# kalman.net
KiCad netlist of a schematic drawn in EAGLE
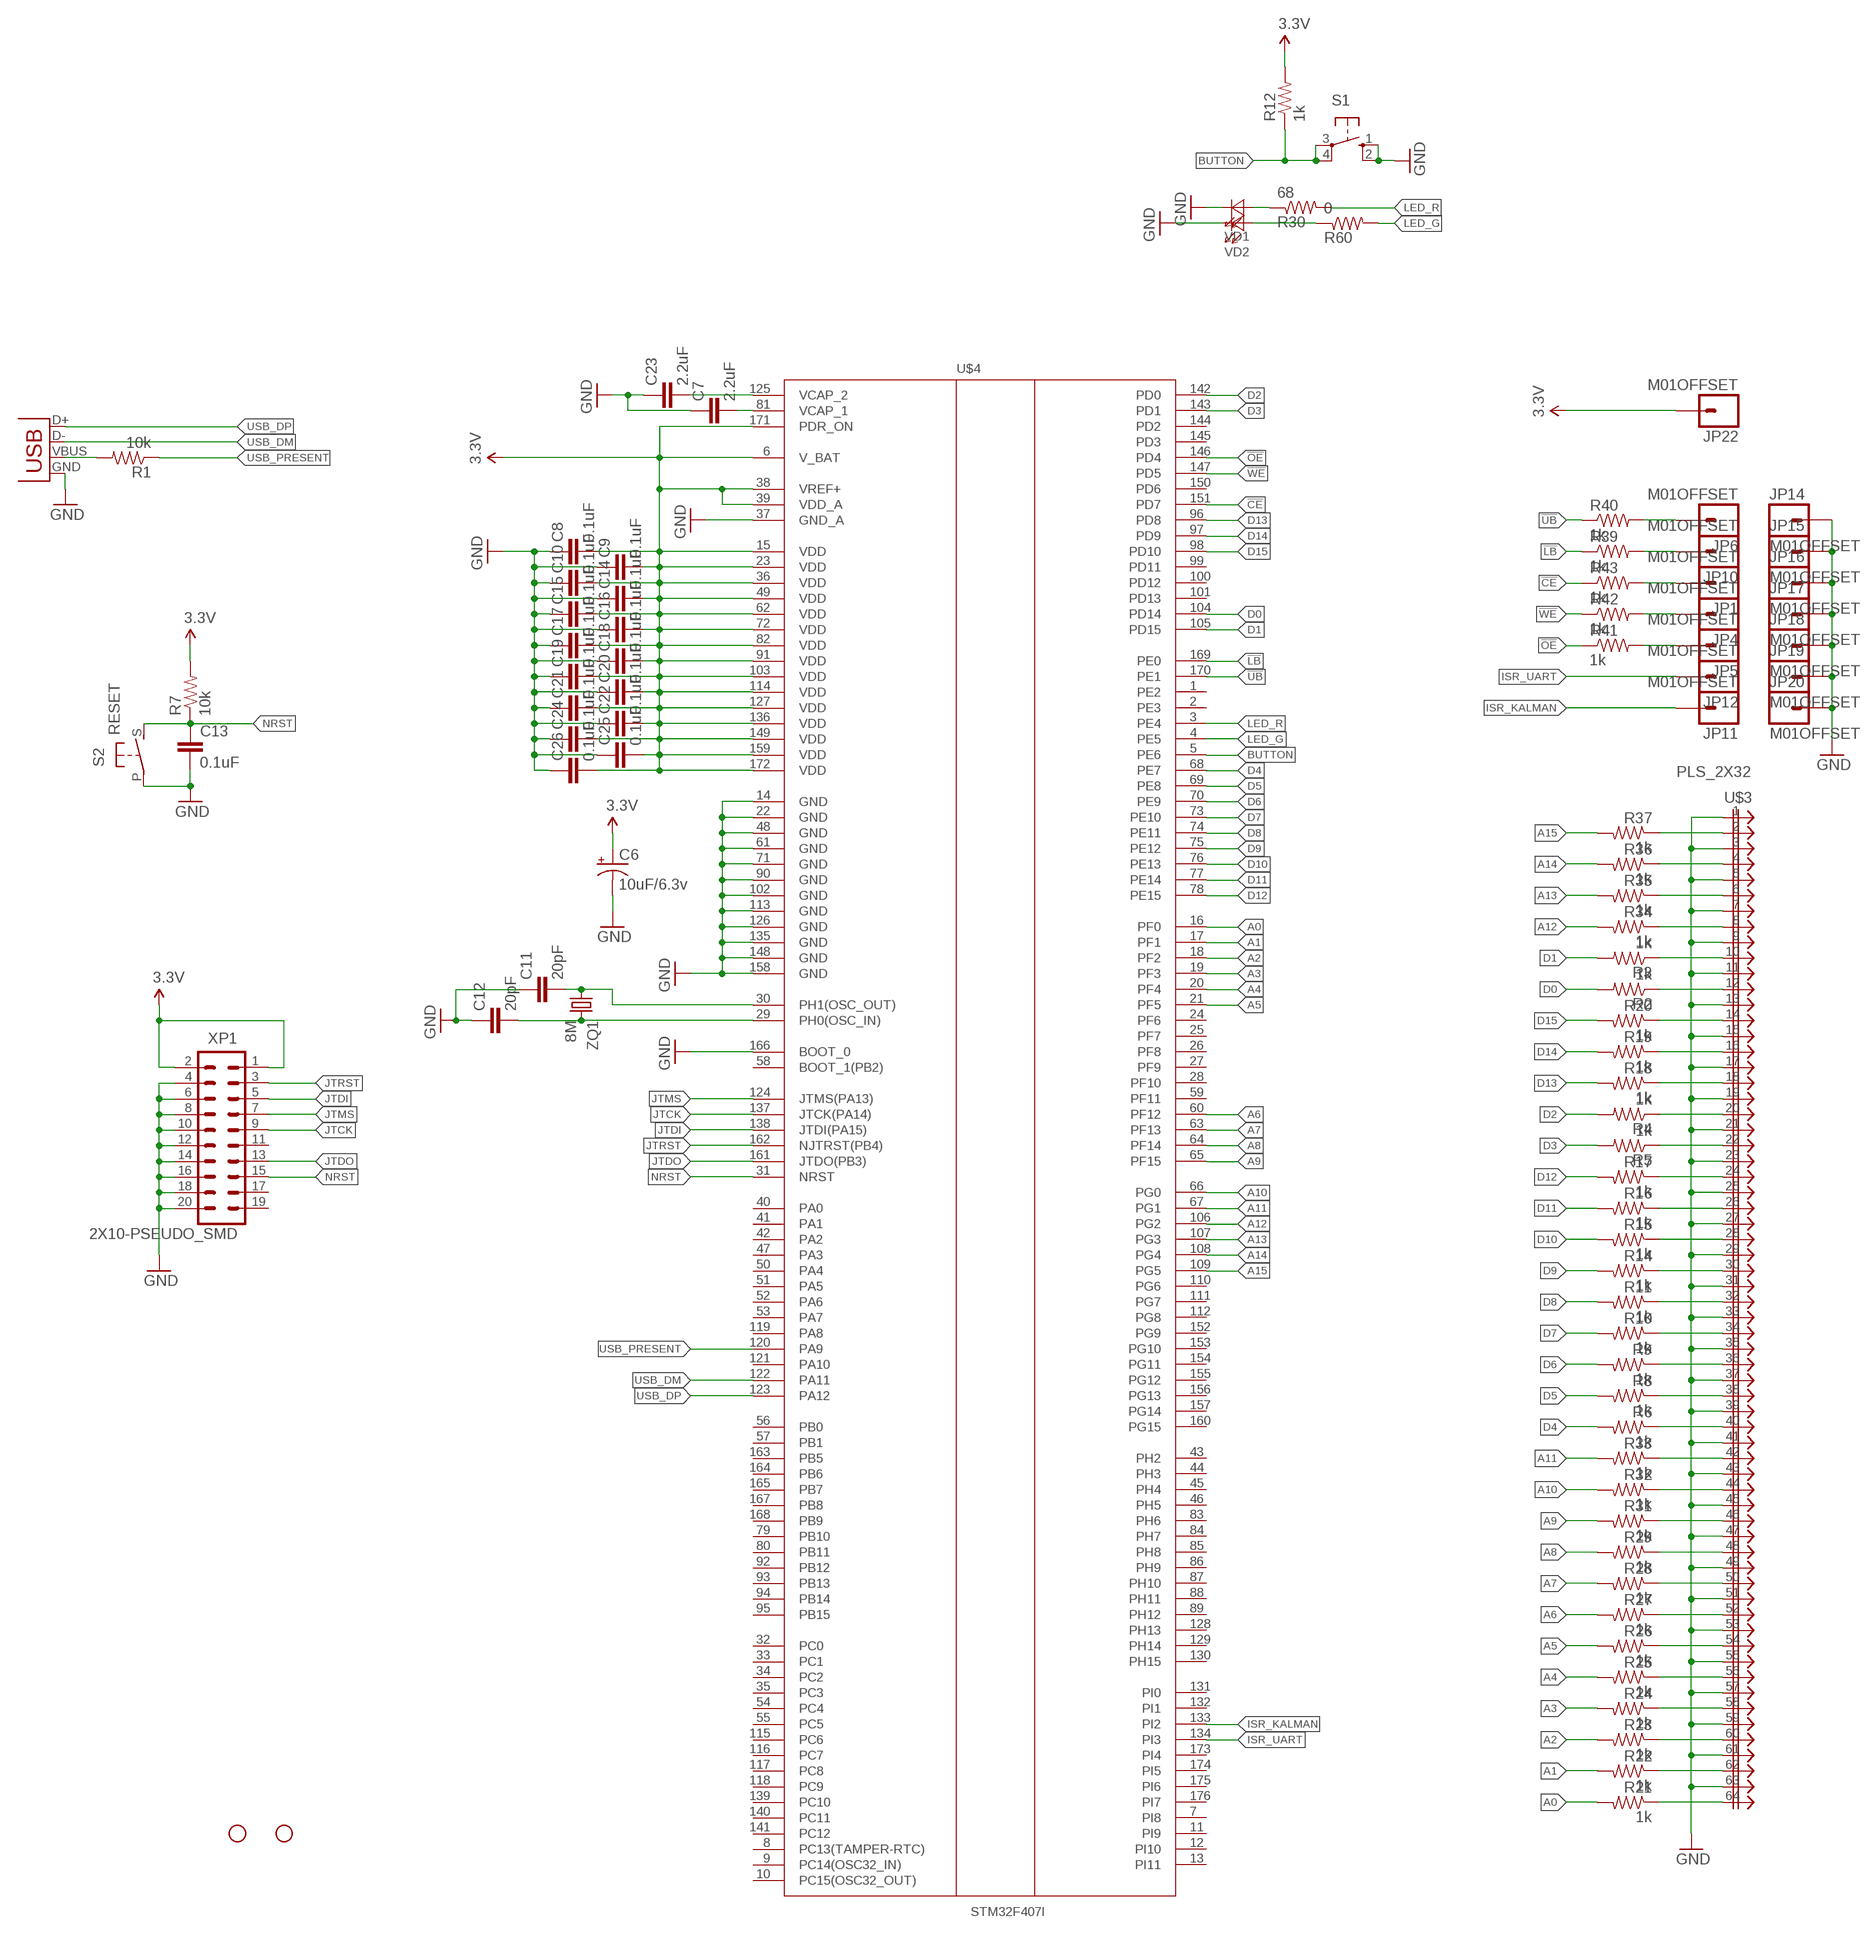
[diagram p0: schematic, sheet 1]

(export (version "E")
  (design (tool "Eeschema 10.0.6"))
  (components
    (comp (ref "C6")
      (value "10uF/6.3v")
      (footprint "eagle-import:EIA3216-KIT")
      (libsource (lib "eagle-import") (part "CAP_POL1206-KIT"))
    )
    (comp (ref "C7")
      (value "2.2uF")
      (footprint "eagle-import:0805")
      (libsource (lib "eagle-import") (part "CAP0805"))
    )
    (comp (ref "C8")
      (value "0.1uF")
      (footprint "eagle-import:0805")
      (libsource (lib "eagle-import") (part "CAP0805"))
    )
    (comp (ref "C9")
      (value "0.1uF")
      (footprint "eagle-import:0805")
      (libsource (lib "eagle-import") (part "CAP0805"))
    )
    (comp (ref "C10")
      (value "0.1uF")
      (footprint "eagle-import:0805")
      (libsource (lib "eagle-import") (part "CAP0805"))
    )
    (comp (ref "C11")
      (value "20pF")
      (footprint "eagle-import:0805")
      (libsource (lib "eagle-import") (part "CAP0805"))
    )
    (comp (ref "C12")
      (value "20pF")
      (footprint "eagle-import:0805")
      (libsource (lib "eagle-import") (part "CAP0805"))
    )
    (comp (ref "C13")
      (value "0.1uF")
      (footprint "eagle-import:0805")
      (libsource (lib "eagle-import") (part "CAP0805"))
    )
    (comp (ref "C14")
      (value "0.1uF")
      (footprint "eagle-import:0805")
      (libsource (lib "eagle-import") (part "CAP0805"))
    )
    (comp (ref "C15")
      (value "0.1uF")
      (footprint "eagle-import:0805")
      (libsource (lib "eagle-import") (part "CAP0805"))
    )
    (comp (ref "C16")
      (value "0.1uF")
      (footprint "eagle-import:0805")
      (libsource (lib "eagle-import") (part "CAP0805"))
    )
    (comp (ref "C17")
      (value "0.1uF")
      (footprint "eagle-import:0805")
      (libsource (lib "eagle-import") (part "CAP0805"))
    )
    (comp (ref "C18")
      (value "0.1uF")
      (footprint "eagle-import:0805")
      (libsource (lib "eagle-import") (part "CAP0805"))
    )
    (comp (ref "C19")
      (value "0.1uF")
      (footprint "eagle-import:0805")
      (libsource (lib "eagle-import") (part "CAP0805"))
    )
    (comp (ref "C20")
      (value "0.1uF")
      (footprint "eagle-import:0805")
      (libsource (lib "eagle-import") (part "CAP0805"))
    )
    (comp (ref "C21")
      (value "0.1uF")
      (footprint "eagle-import:0805")
      (libsource (lib "eagle-import") (part "CAP0805"))
    )
    (comp (ref "C22")
      (value "0.1uF")
      (footprint "eagle-import:0805")
      (libsource (lib "eagle-import") (part "CAP0805"))
    )
    (comp (ref "C23")
      (value "2.2uF")
      (footprint "eagle-import:0805")
      (libsource (lib "eagle-import") (part "CAP0805"))
    )
    (comp (ref "C24")
      (value "0.1uF")
      (footprint "eagle-import:0805")
      (libsource (lib "eagle-import") (part "CAP0805"))
    )
    (comp (ref "C25")
      (value "0.1uF")
      (footprint "eagle-import:0805")
      (libsource (lib "eagle-import") (part "CAP0805"))
    )
    (comp (ref "C26")
      (value "0.1uF")
      (footprint "eagle-import:0805")
      (libsource (lib "eagle-import") (part "CAP0805"))
    )
    (comp (ref "JP1")
      (value "M01OFFSET")
      (footprint "eagle-import:1X01_OFFSET")
      (libsource (lib "eagle-import") (part "M01OFFSET"))
    )
    (comp (ref "JP4")
      (value "M01OFFSET")
      (footprint "eagle-import:1X01_OFFSET")
      (libsource (lib "eagle-import") (part "M01OFFSET"))
    )
    (comp (ref "JP5")
      (value "M01OFFSET")
      (footprint "eagle-import:1X01_OFFSET")
      (libsource (lib "eagle-import") (part "M01OFFSET"))
    )
    (comp (ref "JP6")
      (value "M01OFFSET")
      (footprint "eagle-import:1X01_OFFSET")
      (libsource (lib "eagle-import") (part "M01OFFSET"))
    )
    (comp (ref "JP7")
      (value "STAND-OFF")
      (footprint "eagle-import:STAND-OFF")
      (libsource (lib "eagle-import") (part "STAND-OFF"))
    )
    (comp (ref "JP8")
      (value "STAND-OFF")
      (footprint "eagle-import:STAND-OFF")
      (libsource (lib "eagle-import") (part "STAND-OFF"))
    )
    (comp (ref "JP10")
      (value "M01OFFSET")
      (footprint "eagle-import:1X01_OFFSET")
      (libsource (lib "eagle-import") (part "M01OFFSET"))
    )
    (comp (ref "JP11")
      (value "M01OFFSET")
      (footprint "eagle-import:1X01_OFFSET")
      (libsource (lib "eagle-import") (part "M01OFFSET"))
    )
    (comp (ref "JP12")
      (value "M01OFFSET")
      (footprint "eagle-import:1X01_OFFSET")
      (libsource (lib "eagle-import") (part "M01OFFSET"))
    )
    (comp (ref "JP14")
      (value "M01OFFSET")
      (footprint "eagle-import:1X01_OFFSET")
      (libsource (lib "eagle-import") (part "M01OFFSET"))
    )
    (comp (ref "JP15")
      (value "M01OFFSET")
      (footprint "eagle-import:1X01_OFFSET")
      (libsource (lib "eagle-import") (part "M01OFFSET"))
    )
    (comp (ref "JP16")
      (value "M01OFFSET")
      (footprint "eagle-import:1X01_OFFSET")
      (libsource (lib "eagle-import") (part "M01OFFSET"))
    )
    (comp (ref "JP17")
      (value "M01OFFSET")
      (footprint "eagle-import:1X01_OFFSET")
      (libsource (lib "eagle-import") (part "M01OFFSET"))
    )
    (comp (ref "JP18")
      (value "M01OFFSET")
      (footprint "eagle-import:1X01_OFFSET")
      (libsource (lib "eagle-import") (part "M01OFFSET"))
    )
    (comp (ref "JP19")
      (value "M01OFFSET")
      (footprint "eagle-import:1X01_OFFSET")
      (libsource (lib "eagle-import") (part "M01OFFSET"))
    )
    (comp (ref "JP20")
      (value "M01OFFSET")
      (footprint "eagle-import:1X01_OFFSET")
      (libsource (lib "eagle-import") (part "M01OFFSET"))
    )
    (comp (ref "JP22")
      (value "M01OFFSET")
      (footprint "eagle-import:1X01_OFFSET")
      (libsource (lib "eagle-import") (part "M01OFFSET"))
    )
    (comp (ref "R1")
      (value "10k")
      (footprint "eagle-import:0805")
      (libsource (lib "eagle-import") (part "RESISTOR0805-RES"))
    )
    (comp (ref "R2")
      (value "1k")
      (footprint "eagle-import:0805")
      (libsource (lib "eagle-import") (part "RESISTOR0805-RES"))
    )
    (comp (ref "R3")
      (value "1k")
      (footprint "eagle-import:0805")
      (libsource (lib "eagle-import") (part "RESISTOR0805-RES"))
    )
    (comp (ref "R4")
      (value "1k")
      (footprint "eagle-import:0805")
      (libsource (lib "eagle-import") (part "RESISTOR0805-RES"))
    )
    (comp (ref "R5")
      (value "1k")
      (footprint "eagle-import:0805")
      (libsource (lib "eagle-import") (part "RESISTOR0805-RES"))
    )
    (comp (ref "R6")
      (value "1k")
      (footprint "eagle-import:0805")
      (libsource (lib "eagle-import") (part "RESISTOR0805-RES"))
    )
    (comp (ref "R7")
      (value "10k")
      (footprint "eagle-import:0805")
      (libsource (lib "eagle-import") (part "RESISTOR0805-RES"))
    )
    (comp (ref "R8")
      (value "1k")
      (footprint "eagle-import:0805")
      (libsource (lib "eagle-import") (part "RESISTOR0805-RES"))
    )
    (comp (ref "R9")
      (value "1k")
      (footprint "eagle-import:0805")
      (libsource (lib "eagle-import") (part "RESISTOR0805-RES"))
    )
    (comp (ref "R10")
      (value "1k")
      (footprint "eagle-import:0805")
      (libsource (lib "eagle-import") (part "RESISTOR0805-RES"))
    )
    (comp (ref "R11")
      (value "1k")
      (footprint "eagle-import:0805")
      (libsource (lib "eagle-import") (part "RESISTOR0805-RES"))
    )
    (comp (ref "R12")
      (value "1k")
      (footprint "eagle-import:0805")
      (libsource (lib "eagle-import") (part "RESISTOR0805-RES"))
    )
    (comp (ref "R14")
      (value "1k")
      (footprint "eagle-import:0805")
      (libsource (lib "eagle-import") (part "RESISTOR0805-RES"))
    )
    (comp (ref "R15")
      (value "1k")
      (footprint "eagle-import:0805")
      (libsource (lib "eagle-import") (part "RESISTOR0805-RES"))
    )
    (comp (ref "R16")
      (value "1k")
      (footprint "eagle-import:0805")
      (libsource (lib "eagle-import") (part "RESISTOR0805-RES"))
    )
    (comp (ref "R17")
      (value "1k")
      (footprint "eagle-import:0805")
      (libsource (lib "eagle-import") (part "RESISTOR0805-RES"))
    )
    (comp (ref "R18")
      (value "1k")
      (footprint "eagle-import:0805")
      (libsource (lib "eagle-import") (part "RESISTOR0805-RES"))
    )
    (comp (ref "R19")
      (value "1k")
      (footprint "eagle-import:0805")
      (libsource (lib "eagle-import") (part "RESISTOR0805-RES"))
    )
    (comp (ref "R20")
      (value "1k")
      (footprint "eagle-import:0805")
      (libsource (lib "eagle-import") (part "RESISTOR0805-RES"))
    )
    (comp (ref "R21")
      (value "1k")
      (footprint "eagle-import:0805")
      (libsource (lib "eagle-import") (part "RESISTOR0805-RES"))
    )
    (comp (ref "R22")
      (value "1k")
      (footprint "eagle-import:0805")
      (libsource (lib "eagle-import") (part "RESISTOR0805-RES"))
    )
    (comp (ref "R23")
      (value "1k")
      (footprint "eagle-import:0805")
      (libsource (lib "eagle-import") (part "RESISTOR0805-RES"))
    )
    (comp (ref "R24")
      (value "1k")
      (footprint "eagle-import:0805")
      (libsource (lib "eagle-import") (part "RESISTOR0805-RES"))
    )
    (comp (ref "R25")
      (value "1k")
      (footprint "eagle-import:0805")
      (libsource (lib "eagle-import") (part "RESISTOR0805-RES"))
    )
    (comp (ref "R26")
      (value "1k")
      (footprint "eagle-import:0805")
      (libsource (lib "eagle-import") (part "RESISTOR0805-RES"))
    )
    (comp (ref "R27")
      (value "1k")
      (footprint "eagle-import:0805")
      (libsource (lib "eagle-import") (part "RESISTOR0805-RES"))
    )
    (comp (ref "R28")
      (value "1k")
      (footprint "eagle-import:0805")
      (libsource (lib "eagle-import") (part "RESISTOR0805-RES"))
    )
    (comp (ref "R29")
      (value "1k")
      (footprint "eagle-import:0805")
      (libsource (lib "eagle-import") (part "RESISTOR0805-RES"))
    )
    (comp (ref "R30")
      (value "68")
      (footprint "eagle-import:0805")
      (libsource (lib "eagle-import") (part "RESISTOR0805-RES"))
    )
    (comp (ref "R31")
      (value "1k")
      (footprint "eagle-import:0805")
      (libsource (lib "eagle-import") (part "RESISTOR0805-RES"))
    )
    (comp (ref "R32")
      (value "1k")
      (footprint "eagle-import:0805")
      (libsource (lib "eagle-import") (part "RESISTOR0805-RES"))
    )
    (comp (ref "R33")
      (value "1k")
      (footprint "eagle-import:0805")
      (libsource (lib "eagle-import") (part "RESISTOR0805-RES"))
    )
    (comp (ref "R34")
      (value "1k")
      (footprint "eagle-import:0805")
      (libsource (lib "eagle-import") (part "RESISTOR0805-RES"))
    )
    (comp (ref "R35")
      (value "1k")
      (footprint "eagle-import:0805")
      (libsource (lib "eagle-import") (part "RESISTOR0805-RES"))
    )
    (comp (ref "R36")
      (value "1k")
      (footprint "eagle-import:0805")
      (libsource (lib "eagle-import") (part "RESISTOR0805-RES"))
    )
    (comp (ref "R37")
      (value "1k")
      (footprint "eagle-import:0805")
      (libsource (lib "eagle-import") (part "RESISTOR0805-RES"))
    )
    (comp (ref "R39")
      (value "1k")
      (footprint "eagle-import:0805")
      (libsource (lib "eagle-import") (part "RESISTOR0805-RES"))
    )
    (comp (ref "R40")
      (value "1k")
      (footprint "eagle-import:0805")
      (libsource (lib "eagle-import") (part "RESISTOR0805-RES"))
    )
    (comp (ref "R41")
      (value "1k")
      (footprint "eagle-import:0805")
      (libsource (lib "eagle-import") (part "RESISTOR0805-RES"))
    )
    (comp (ref "R42")
      (value "1k")
      (footprint "eagle-import:0805")
      (libsource (lib "eagle-import") (part "RESISTOR0805-RES"))
    )
    (comp (ref "R43")
      (value "1k")
      (footprint "eagle-import:0805")
      (libsource (lib "eagle-import") (part "RESISTOR0805-RES"))
    )
    (comp (ref "R60")
      (value "0")
      (footprint "eagle-import:0805")
      (libsource (lib "eagle-import") (part "RESISTOR0805-RES"))
    )
    (comp (ref "S1")
      (value "10-XX")
      (footprint "eagle-import:B3F-10XX")
      (fields (field (name "MPN") "B3F-1000"))
      (libsource (lib "eagle-import") (part "10-XX"))
    )
    (comp (ref "S2")
      (value "RESET")
      (footprint "eagle-import:BUTTON_6X3.5")
      (libsource (lib "eagle-import") (part "BUTTON_6X3.5"))
    )
    (comp (ref "U$3")
      (value "PLS_2X32")
      (footprint "eagle-import:PLS_2X32_PSEUDOSMD")
      (libsource (lib "eagle-import") (part "PLS_2X32"))
    )
    (comp (ref "U$4")
      (value "STM32F407I")
      (footprint "eagle-import:TQFP176(1.5X0.25)")
      (libsource (lib "eagle-import") (part "STM32F407I"))
    )
    (comp (ref "VD1")
      (value "LED1206")
      (footprint "eagle-import:LED-1206")
      (libsource (lib "eagle-import") (part "LED1206"))
    )
    (comp (ref "VD2")
      (value "LED1206")
      (footprint "eagle-import:LED-1206")
      (libsource (lib "eagle-import") (part "LED1206"))
    )
    (comp (ref "X1")
      (value "USB-SMD-NS")
      (footprint "eagle-import:USB-MINIB-NOSTOP")
      (libsource (lib "eagle-import") (part "USB-SMD-NS"))
    )
    (comp (ref "XP1")
      (value "2X10-PSEUDO_SMD")
      (footprint "eagle-import:PLD_2X10_PSEUDOSMD")
      (libsource (lib "eagle-import") (part "2X10-PSEUDO_SMD"))
    )
    (comp (ref "ZQ1")
      (value "8M")
      (footprint "eagle-import:CTS406")
      (libsource (lib "eagle-import") (part "CRYSTALCTS406"))
    )
  )
  (nets
    (net (code "1") (name "/~{CE}") (class "Default")
      (node (ref "R43") (pin "1") (pinfunction "1_1") (pintype "passive"))
      (node (ref "U$4") (pin "151") (pinfunction "PD7_151") (pintype "bidirectional"))
    )
    (net (code "2") (name "/~{LB}") (class "Default")
      (node (ref "R39") (pin "1") (pinfunction "1_1") (pintype "passive"))
      (node (ref "U$4") (pin "169") (pinfunction "PE0_169") (pintype "bidirectional"))
    )
    (net (code "3") (name "/~{OE}") (class "Default")
      (node (ref "R41") (pin "1") (pinfunction "1_1") (pintype "passive"))
      (node (ref "U$4") (pin "146") (pinfunction "PD4_146") (pintype "bidirectional"))
    )
    (net (code "4") (name "/~{UB}") (class "Default")
      (node (ref "R40") (pin "1") (pinfunction "1_1") (pintype "passive"))
      (node (ref "U$4") (pin "170") (pinfunction "PE1_170") (pintype "bidirectional"))
    )
    (net (code "5") (name "/~{WE}") (class "Default")
      (node (ref "R42") (pin "1") (pinfunction "1_1") (pintype "passive"))
      (node (ref "U$4") (pin "147") (pinfunction "PD5_147") (pintype "bidirectional"))
    )
    (net (code "6") (name "3.3V") (class "Default")
      (node (ref "C10") (pin "2") (pinfunction "2_2") (pintype "passive"))
      (node (ref "C14") (pin "2") (pinfunction "2_2") (pintype "passive"))
      (node (ref "C15") (pin "2") (pinfunction "2_2") (pintype "passive"))
      (node (ref "C16") (pin "2") (pinfunction "2_2") (pintype "passive"))
      (node (ref "C17") (pin "2") (pinfunction "2_2") (pintype "passive"))
      (node (ref "C18") (pin "2") (pinfunction "2_2") (pintype "passive"))
      (node (ref "C19") (pin "2") (pinfunction "2_2") (pintype "passive"))
      (node (ref "C20") (pin "2") (pinfunction "2_2") (pintype "passive"))
      (node (ref "C21") (pin "2") (pinfunction "2_2") (pintype "passive"))
      (node (ref "C22") (pin "2") (pinfunction "2_2") (pintype "passive"))
      (node (ref "C24") (pin "2") (pinfunction "2_2") (pintype "passive"))
      (node (ref "C25") (pin "2") (pinfunction "2_2") (pintype "passive"))
      (node (ref "C26") (pin "2") (pinfunction "2_2") (pintype "passive"))
      (node (ref "C6") (pin "A") (pinfunction "+_A") (pintype "passive"))
      (node (ref "C8") (pin "2") (pinfunction "2_2") (pintype "passive"))
      (node (ref "C9") (pin "2") (pinfunction "2_2") (pintype "passive"))
      (node (ref "JP22") (pin "1") (pinfunction "1_1") (pintype "passive"))
      (node (ref "R12") (pin "2") (pinfunction "2_2") (pintype "passive"))
      (node (ref "R7") (pin "2") (pinfunction "2_2") (pintype "passive"))
      (node (ref "U$4") (pin "103") (pinfunction "VDD_103") (pintype "power_in"))
      (node (ref "U$4") (pin "114") (pinfunction "VDD_114") (pintype "power_in"))
      (node (ref "U$4") (pin "127") (pinfunction "VDD_127") (pintype "power_in"))
      (node (ref "U$4") (pin "136") (pinfunction "VDD_136") (pintype "power_in"))
      (node (ref "U$4") (pin "149") (pinfunction "VDD_149") (pintype "power_in"))
      (node (ref "U$4") (pin "15") (pinfunction "VDD_15") (pintype "power_in"))
      (node (ref "U$4") (pin "159") (pinfunction "VDD_159") (pintype "power_in"))
      (node (ref "U$4") (pin "171") (pinfunction "PDR_ON_171") (pintype "power_in"))
      (node (ref "U$4") (pin "172") (pinfunction "VDD_172") (pintype "power_in"))
      (node (ref "U$4") (pin "23") (pinfunction "VDD_23") (pintype "power_in"))
      (node (ref "U$4") (pin "36") (pinfunction "VDD_36") (pintype "power_in"))
      (node (ref "U$4") (pin "38") (pinfunction "VREF+_38") (pintype "power_in"))
      (node (ref "U$4") (pin "39") (pinfunction "VDD_A_39") (pintype "power_in"))
      (node (ref "U$4") (pin "49") (pinfunction "VDD_49") (pintype "power_in"))
      (node (ref "U$4") (pin "6") (pinfunction "V_BAT_6") (pintype "power_in"))
      (node (ref "U$4") (pin "62") (pinfunction "VDD_62") (pintype "power_in"))
      (node (ref "U$4") (pin "72") (pinfunction "VDD_72") (pintype "power_in"))
      (node (ref "U$4") (pin "82") (pinfunction "VDD_82") (pintype "power_in"))
      (node (ref "U$4") (pin "91") (pinfunction "VDD_91") (pintype "power_in"))
      (node (ref "XP1") (pin "1") (pinfunction "1_1") (pintype "passive"))
      (node (ref "XP1") (pin "2") (pinfunction "2_2") (pintype "passive"))
    )
    (net (code "7") (name "A0") (class "Default")
      (node (ref "R21") (pin "2") (pinfunction "2_2") (pintype "passive"))
      (node (ref "U$4") (pin "16") (pinfunction "PF0_16") (pintype "bidirectional"))
    )
    (net (code "8") (name "A1") (class "Default")
      (node (ref "R22") (pin "2") (pinfunction "2_2") (pintype "passive"))
      (node (ref "U$4") (pin "17") (pinfunction "PF1_17") (pintype "bidirectional"))
    )
    (net (code "9") (name "A2") (class "Default")
      (node (ref "R23") (pin "2") (pinfunction "2_2") (pintype "passive"))
      (node (ref "U$4") (pin "18") (pinfunction "PF2_18") (pintype "bidirectional"))
    )
    (net (code "10") (name "A3") (class "Default")
      (node (ref "R24") (pin "2") (pinfunction "2_2") (pintype "passive"))
      (node (ref "U$4") (pin "19") (pinfunction "PF3_19") (pintype "bidirectional"))
    )
    (net (code "11") (name "A4") (class "Default")
      (node (ref "R25") (pin "2") (pinfunction "2_2") (pintype "passive"))
      (node (ref "U$4") (pin "20") (pinfunction "PF4_20") (pintype "bidirectional"))
    )
    (net (code "12") (name "A5") (class "Default")
      (node (ref "R26") (pin "2") (pinfunction "2_2") (pintype "passive"))
      (node (ref "U$4") (pin "21") (pinfunction "PF5_21") (pintype "bidirectional"))
    )
    (net (code "13") (name "A6") (class "Default")
      (node (ref "R27") (pin "2") (pinfunction "2_2") (pintype "passive"))
      (node (ref "U$4") (pin "60") (pinfunction "PF12_60") (pintype "bidirectional"))
    )
    (net (code "14") (name "A7") (class "Default")
      (node (ref "R28") (pin "2") (pinfunction "2_2") (pintype "passive"))
      (node (ref "U$4") (pin "63") (pinfunction "PF13_63") (pintype "bidirectional"))
    )
    (net (code "15") (name "A8") (class "Default")
      (node (ref "R29") (pin "2") (pinfunction "2_2") (pintype "passive"))
      (node (ref "U$4") (pin "64") (pinfunction "PF14_64") (pintype "bidirectional"))
    )
    (net (code "16") (name "A9") (class "Default")
      (node (ref "R31") (pin "2") (pinfunction "2_2") (pintype "passive"))
      (node (ref "U$4") (pin "65") (pinfunction "PF15_65") (pintype "bidirectional"))
    )
    (net (code "17") (name "A10") (class "Default")
      (node (ref "R32") (pin "2") (pinfunction "2_2") (pintype "passive"))
      (node (ref "U$4") (pin "66") (pinfunction "PG0_66") (pintype "bidirectional"))
    )
    (net (code "18") (name "A11") (class "Default")
      (node (ref "R33") (pin "2") (pinfunction "2_2") (pintype "passive"))
      (node (ref "U$4") (pin "67") (pinfunction "PG1_67") (pintype "bidirectional"))
    )
    (net (code "19") (name "A12") (class "Default")
      (node (ref "R34") (pin "2") (pinfunction "2_2") (pintype "passive"))
      (node (ref "U$4") (pin "106") (pinfunction "PG2_106") (pintype "bidirectional"))
    )
    (net (code "20") (name "A13") (class "Default")
      (node (ref "R35") (pin "2") (pinfunction "2_2") (pintype "passive"))
      (node (ref "U$4") (pin "107") (pinfunction "PG3_107") (pintype "bidirectional"))
    )
    (net (code "21") (name "A14") (class "Default")
      (node (ref "R36") (pin "2") (pinfunction "2_2") (pintype "passive"))
      (node (ref "U$4") (pin "108") (pinfunction "PG4_108") (pintype "bidirectional"))
    )
    (net (code "22") (name "A15") (class "Default")
      (node (ref "R37") (pin "2") (pinfunction "2_2") (pintype "passive"))
      (node (ref "U$4") (pin "109") (pinfunction "PG5_109") (pintype "bidirectional"))
    )
    (net (code "23") (name "BUTTON") (class "Default")
      (node (ref "R12") (pin "1") (pinfunction "1_1") (pintype "passive"))
      (node (ref "S1") (pin "3") (pinfunction "P_3") (pintype "passive"))
      (node (ref "S1") (pin "4") (pinfunction "P1_4") (pintype "passive"))
      (node (ref "U$4") (pin "5") (pinfunction "PE6_5") (pintype "bidirectional"))
    )
    (net (code "24") (name "D0") (class "Default")
      (node (ref "R2") (pin "2") (pinfunction "2_2") (pintype "passive"))
      (node (ref "U$4") (pin "104") (pinfunction "PD14_104") (pintype "bidirectional"))
    )
    (net (code "25") (name "D1") (class "Default")
      (node (ref "R3") (pin "2") (pinfunction "2_2") (pintype "passive"))
      (node (ref "U$4") (pin "105") (pinfunction "PD15_105") (pintype "bidirectional"))
    )
    (net (code "26") (name "D2") (class "Default")
      (node (ref "R4") (pin "2") (pinfunction "2_2") (pintype "passive"))
      (node (ref "U$4") (pin "142") (pinfunction "PD0_142") (pintype "bidirectional"))
    )
    (net (code "27") (name "D3") (class "Default")
      (node (ref "R5") (pin "2") (pinfunction "2_2") (pintype "passive"))
      (node (ref "U$4") (pin "143") (pinfunction "PD1_143") (pintype "bidirectional"))
    )
    (net (code "28") (name "D4") (class "Default")
      (node (ref "R6") (pin "2") (pinfunction "2_2") (pintype "passive"))
      (node (ref "U$4") (pin "68") (pinfunction "PE7_68") (pintype "bidirectional"))
    )
    (net (code "29") (name "D5") (class "Default")
      (node (ref "R8") (pin "2") (pinfunction "2_2") (pintype "passive"))
      (node (ref "U$4") (pin "69") (pinfunction "PE8_69") (pintype "bidirectional"))
    )
    (net (code "30") (name "D6") (class "Default")
      (node (ref "R9") (pin "2") (pinfunction "2_2") (pintype "passive"))
      (node (ref "U$4") (pin "70") (pinfunction "PE9_70") (pintype "bidirectional"))
    )
    (net (code "31") (name "D7") (class "Default")
      (node (ref "R10") (pin "2") (pinfunction "2_2") (pintype "passive"))
      (node (ref "U$4") (pin "73") (pinfunction "PE10_73") (pintype "bidirectional"))
    )
    (net (code "32") (name "D8") (class "Default")
      (node (ref "R11") (pin "2") (pinfunction "2_2") (pintype "passive"))
      (node (ref "U$4") (pin "74") (pinfunction "PE11_74") (pintype "bidirectional"))
    )
    (net (code "33") (name "D9") (class "Default")
      (node (ref "R14") (pin "2") (pinfunction "2_2") (pintype "passive"))
      (node (ref "U$4") (pin "75") (pinfunction "PE12_75") (pintype "bidirectional"))
    )
    (net (code "34") (name "D10") (class "Default")
      (node (ref "R15") (pin "2") (pinfunction "2_2") (pintype "passive"))
      (node (ref "U$4") (pin "76") (pinfunction "PE13_76") (pintype "bidirectional"))
    )
    (net (code "35") (name "D11") (class "Default")
      (node (ref "R16") (pin "2") (pinfunction "2_2") (pintype "passive"))
      (node (ref "U$4") (pin "77") (pinfunction "PE14_77") (pintype "bidirectional"))
    )
    (net (code "36") (name "D12") (class "Default")
      (node (ref "R17") (pin "2") (pinfunction "2_2") (pintype "passive"))
      (node (ref "U$4") (pin "78") (pinfunction "PE15_78") (pintype "bidirectional"))
    )
    (net (code "37") (name "D13") (class "Default")
      (node (ref "R18") (pin "2") (pinfunction "2_2") (pintype "passive"))
      (node (ref "U$4") (pin "96") (pinfunction "PD8_96") (pintype "bidirectional"))
    )
    (net (code "38") (name "D14") (class "Default")
      (node (ref "R19") (pin "2") (pinfunction "2_2") (pintype "passive"))
      (node (ref "U$4") (pin "97") (pinfunction "PD9_97") (pintype "bidirectional"))
    )
    (net (code "39") (name "D15") (class "Default")
      (node (ref "R20") (pin "2") (pinfunction "2_2") (pintype "passive"))
      (node (ref "U$4") (pin "98") (pinfunction "PD10_98") (pintype "bidirectional"))
    )
    (net (code "40") (name "GND") (class "Default")
      (node (ref "C10") (pin "1") (pinfunction "1_1") (pintype "passive"))
      (node (ref "C11") (pin "1") (pinfunction "1_1") (pintype "passive"))
      (node (ref "C12") (pin "1") (pinfunction "1_1") (pintype "passive"))
      (node (ref "C13") (pin "2") (pinfunction "2_2") (pintype "passive"))
      (node (ref "C14") (pin "1") (pinfunction "1_1") (pintype "passive"))
      (node (ref "C15") (pin "1") (pinfunction "1_1") (pintype "passive"))
      (node (ref "C16") (pin "1") (pinfunction "1_1") (pintype "passive"))
      (node (ref "C17") (pin "1") (pinfunction "1_1") (pintype "passive"))
      (node (ref "C18") (pin "1") (pinfunction "1_1") (pintype "passive"))
      (node (ref "C19") (pin "1") (pinfunction "1_1") (pintype "passive"))
      (node (ref "C20") (pin "1") (pinfunction "1_1") (pintype "passive"))
      (node (ref "C21") (pin "1") (pinfunction "1_1") (pintype "passive"))
      (node (ref "C22") (pin "1") (pinfunction "1_1") (pintype "passive"))
      (node (ref "C23") (pin "1") (pinfunction "1_1") (pintype "passive"))
      (node (ref "C24") (pin "1") (pinfunction "1_1") (pintype "passive"))
      (node (ref "C25") (pin "1") (pinfunction "1_1") (pintype "passive"))
      (node (ref "C26") (pin "1") (pinfunction "1_1") (pintype "passive"))
      (node (ref "C6") (pin "C") (pinfunction "-_C") (pintype "passive"))
      (node (ref "C7") (pin "1") (pinfunction "1_1") (pintype "passive"))
      (node (ref "C8") (pin "1") (pinfunction "1_1") (pintype "passive"))
      (node (ref "C9") (pin "1") (pinfunction "1_1") (pintype "passive"))
      (node (ref "JP14") (pin "1") (pinfunction "1_1") (pintype "passive"))
      (node (ref "JP15") (pin "1") (pinfunction "1_1") (pintype "passive"))
      (node (ref "JP16") (pin "1") (pinfunction "1_1") (pintype "passive"))
      (node (ref "JP17") (pin "1") (pinfunction "1_1") (pintype "passive"))
      (node (ref "JP18") (pin "1") (pinfunction "1_1") (pintype "passive"))
      (node (ref "JP19") (pin "1") (pinfunction "1_1") (pintype "passive"))
      (node (ref "JP20") (pin "1") (pinfunction "1_1") (pintype "passive"))
      (node (ref "S1") (pin "1") (pinfunction "S_1") (pintype "passive"))
      (node (ref "S1") (pin "2") (pinfunction "S1_2") (pintype "passive"))
      (node (ref "S2") (pin "P") (pinfunction "P_P") (pintype "passive"))
      (node (ref "U$3") (pin "1") (pinfunction "1_1") (pintype "passive"))
      (node (ref "U$3") (pin "11") (pinfunction "11_11") (pintype "passive"))
      (node (ref "U$3") (pin "13") (pinfunction "13_13") (pintype "passive"))
      (node (ref "U$3") (pin "15") (pinfunction "15_15") (pintype "passive"))
      (node (ref "U$3") (pin "17") (pinfunction "17_17") (pintype "passive"))
      (node (ref "U$3") (pin "19") (pinfunction "19_19") (pintype "passive"))
      (node (ref "U$3") (pin "21") (pinfunction "21_21") (pintype "passive"))
      (node (ref "U$3") (pin "23") (pinfunction "23_23") (pintype "passive"))
      (node (ref "U$3") (pin "25") (pinfunction "25_25") (pintype "passive"))
      (node (ref "U$3") (pin "27") (pinfunction "27_27") (pintype "passive"))
      (node (ref "U$3") (pin "29") (pinfunction "29_29") (pintype "passive"))
      (node (ref "U$3") (pin "3") (pinfunction "3_3") (pintype "passive"))
      (node (ref "U$3") (pin "31") (pinfunction "31_31") (pintype "passive"))
      (node (ref "U$3") (pin "33") (pinfunction "33_33") (pintype "passive"))
      (node (ref "U$3") (pin "35") (pinfunction "35_35") (pintype "passive"))
      (node (ref "U$3") (pin "37") (pinfunction "37_37") (pintype "passive"))
      (node (ref "U$3") (pin "39") (pinfunction "39_39") (pintype "passive"))
      (node (ref "U$3") (pin "41") (pinfunction "41_41") (pintype "passive"))
      (node (ref "U$3") (pin "43") (pinfunction "43_43") (pintype "passive"))
      (node (ref "U$3") (pin "45") (pinfunction "45_45") (pintype "passive"))
      (node (ref "U$3") (pin "47") (pinfunction "47_47") (pintype "passive"))
      (node (ref "U$3") (pin "49") (pinfunction "49_49") (pintype "passive"))
      (node (ref "U$3") (pin "5") (pinfunction "5_5") (pintype "passive"))
      (node (ref "U$3") (pin "51") (pinfunction "51_51") (pintype "passive"))
      (node (ref "U$3") (pin "53") (pinfunction "53_53") (pintype "passive"))
      (node (ref "U$3") (pin "55") (pinfunction "55_55") (pintype "passive"))
      (node (ref "U$3") (pin "57") (pinfunction "57_57") (pintype "passive"))
      (node (ref "U$3") (pin "59") (pinfunction "59_59") (pintype "passive"))
      (node (ref "U$3") (pin "61") (pinfunction "61_61") (pintype "passive"))
      (node (ref "U$3") (pin "63") (pinfunction "63_63") (pintype "passive"))
      (node (ref "U$3") (pin "7") (pinfunction "7_7") (pintype "passive"))
      (node (ref "U$3") (pin "9") (pinfunction "9_9") (pintype "passive"))
      (node (ref "U$4") (pin "102") (pinfunction "GND_102") (pintype "power_in"))
      (node (ref "U$4") (pin "113") (pinfunction "GND_113") (pintype "power_in"))
      (node (ref "U$4") (pin "126") (pinfunction "GND_126") (pintype "power_in"))
      (node (ref "U$4") (pin "135") (pinfunction "GND_135") (pintype "power_in"))
      (node (ref "U$4") (pin "14") (pinfunction "GND_14") (pintype "power_in"))
      (node (ref "U$4") (pin "148") (pinfunction "GND_148") (pintype "power_in"))
      (node (ref "U$4") (pin "158") (pinfunction "GND_158") (pintype "power_in"))
      (node (ref "U$4") (pin "166") (pinfunction "BOOT_0_166") (pintype "input"))
      (node (ref "U$4") (pin "22") (pinfunction "GND_22") (pintype "power_in"))
      (node (ref "U$4") (pin "37") (pinfunction "GND_A_37") (pintype "power_in"))
      (node (ref "U$4") (pin "48") (pinfunction "GND_48") (pintype "power_in"))
      (node (ref "U$4") (pin "61") (pinfunction "GND_61") (pintype "power_in"))
      (node (ref "U$4") (pin "71") (pinfunction "GND_71") (pintype "power_in"))
      (node (ref "U$4") (pin "90") (pinfunction "GND_90") (pintype "power_in"))
      (node (ref "VD1") (pin "C") (pinfunction "C_C") (pintype "passive"))
      (node (ref "VD2") (pin "C") (pinfunction "C_C") (pintype "passive"))
      (node (ref "X1") (pin "GND") (pinfunction "GND_GND") (pintype "bidirectional"))
      (node (ref "XP1") (pin "10") (pinfunction "10_10") (pintype "passive"))
      (node (ref "XP1") (pin "12") (pinfunction "12_12") (pintype "passive"))
      (node (ref "XP1") (pin "14") (pinfunction "14_14") (pintype "passive"))
      (node (ref "XP1") (pin "16") (pinfunction "16_16") (pintype "passive"))
      (node (ref "XP1") (pin "18") (pinfunction "18_18") (pintype "passive"))
      (node (ref "XP1") (pin "20") (pinfunction "20_20") (pintype "passive"))
      (node (ref "XP1") (pin "4") (pinfunction "4_4") (pintype "passive"))
      (node (ref "XP1") (pin "6") (pinfunction "6_6") (pintype "passive"))
      (node (ref "XP1") (pin "8") (pinfunction "8_8") (pintype "passive"))
    )
    (net (code "41") (name "ISR_KALMAN") (class "Default")
      (node (ref "JP11") (pin "1") (pinfunction "1_1") (pintype "passive"))
      (node (ref "U$4") (pin "133") (pinfunction "PI2_133") (pintype "bidirectional"))
    )
    (net (code "42") (name "ISR_UART") (class "Default")
      (node (ref "JP12") (pin "1") (pinfunction "1_1") (pintype "passive"))
      (node (ref "U$4") (pin "134") (pinfunction "PI3_134") (pintype "bidirectional"))
    )
    (net (code "43") (name "JTCK") (class "Default")
      (node (ref "U$4") (pin "137") (pinfunction "JTCK(PA14)_137") (pintype "bidirectional"))
      (node (ref "XP1") (pin "9") (pinfunction "9_9") (pintype "passive"))
    )
    (net (code "44") (name "JTDI") (class "Default")
      (node (ref "U$4") (pin "138") (pinfunction "JTDI(PA15)_138") (pintype "bidirectional"))
      (node (ref "XP1") (pin "5") (pinfunction "5_5") (pintype "passive"))
    )
    (net (code "45") (name "JTDO") (class "Default")
      (node (ref "U$4") (pin "161") (pinfunction "JTDO(PB3)_161") (pintype "bidirectional"))
      (node (ref "XP1") (pin "13") (pinfunction "13_13") (pintype "passive"))
    )
    (net (code "46") (name "JTMS") (class "Default")
      (node (ref "U$4") (pin "124") (pinfunction "JTMS(PA13)_124") (pintype "bidirectional"))
      (node (ref "XP1") (pin "7") (pinfunction "7_7") (pintype "passive"))
    )
    (net (code "47") (name "JTRST") (class "Default")
      (node (ref "U$4") (pin "162") (pinfunction "NJTRST(PB4)_162") (pintype "bidirectional"))
      (node (ref "XP1") (pin "3") (pinfunction "3_3") (pintype "passive"))
    )
    (net (code "48") (name "LED_G") (class "Default")
      (node (ref "R60") (pin "2") (pinfunction "2_2") (pintype "passive"))
      (node (ref "U$4") (pin "4") (pinfunction "PE5_4") (pintype "bidirectional"))
    )
    (net (code "49") (name "LED_R") (class "Default")
      (node (ref "R30") (pin "2") (pinfunction "2_2") (pintype "passive"))
      (node (ref "U$4") (pin "3") (pinfunction "PE4_3") (pintype "bidirectional"))
    )
    (net (code "50") (name "NRST") (class "Default")
      (node (ref "C13") (pin "1") (pinfunction "1_1") (pintype "passive"))
      (node (ref "R7") (pin "1") (pinfunction "1_1") (pintype "passive"))
      (node (ref "S2") (pin "S") (pinfunction "S_S") (pintype "passive"))
      (node (ref "U$4") (pin "31") (pinfunction "NRST_31") (pintype "bidirectional"))
      (node (ref "XP1") (pin "15") (pinfunction "15_15") (pintype "passive"))
    )
    (net (code "51") (name "Net-(JP1-Pad1)") (class "Default")
      (node (ref "JP1") (pin "1") (pinfunction "1_1") (pintype "passive"))
      (node (ref "R43") (pin "2") (pinfunction "2_2") (pintype "passive"))
    )
    (net (code "52") (name "Net-(JP4-Pad1)") (class "Default")
      (node (ref "JP4") (pin "1") (pinfunction "1_1") (pintype "passive"))
      (node (ref "R42") (pin "2") (pinfunction "2_2") (pintype "passive"))
    )
    (net (code "53") (name "Net-(JP5-Pad1)") (class "Default")
      (node (ref "JP5") (pin "1") (pinfunction "1_1") (pintype "passive"))
      (node (ref "R41") (pin "2") (pinfunction "2_2") (pintype "passive"))
    )
    (net (code "54") (name "Net-(JP6-Pad1)") (class "Default")
      (node (ref "JP6") (pin "1") (pinfunction "1_1") (pintype "passive"))
      (node (ref "R40") (pin "2") (pinfunction "2_2") (pintype "passive"))
    )
    (net (code "55") (name "Net-(JP10-Pad1)") (class "Default")
      (node (ref "JP10") (pin "1") (pinfunction "1_1") (pintype "passive"))
      (node (ref "R39") (pin "2") (pinfunction "2_2") (pintype "passive"))
    )
    (net (code "56") (name "Net-(R1-Pad2)") (class "Default")
      (node (ref "R1") (pin "2") (pinfunction "2_2") (pintype "passive"))
      (node (ref "X1") (pin "VBUS") (pinfunction "VBUS_VBUS") (pintype "bidirectional"))
    )
    (net (code "57") (name "Net-(R2-Pad1)") (class "Default")
      (node (ref "R2") (pin "1") (pinfunction "1_1") (pintype "passive"))
      (node (ref "U$3") (pin "12") (pinfunction "12_12") (pintype "passive"))
    )
    (net (code "58") (name "Net-(R3-Pad1)") (class "Default")
      (node (ref "R3") (pin "1") (pinfunction "1_1") (pintype "passive"))
      (node (ref "U$3") (pin "10") (pinfunction "10_10") (pintype "passive"))
    )
    (net (code "59") (name "Net-(R4-Pad1)") (class "Default")
      (node (ref "R4") (pin "1") (pinfunction "1_1") (pintype "passive"))
      (node (ref "U$3") (pin "20") (pinfunction "20_20") (pintype "passive"))
    )
    (net (code "60") (name "Net-(R5-Pad1)") (class "Default")
      (node (ref "R5") (pin "1") (pinfunction "1_1") (pintype "passive"))
      (node (ref "U$3") (pin "22") (pinfunction "22_22") (pintype "passive"))
    )
    (net (code "61") (name "Net-(R6-Pad1)") (class "Default")
      (node (ref "R6") (pin "1") (pinfunction "1_1") (pintype "passive"))
      (node (ref "U$3") (pin "40") (pinfunction "40_40") (pintype "passive"))
    )
    (net (code "62") (name "Net-(R8-Pad1)") (class "Default")
      (node (ref "R8") (pin "1") (pinfunction "1_1") (pintype "passive"))
      (node (ref "U$3") (pin "38") (pinfunction "38_38") (pintype "passive"))
    )
    (net (code "63") (name "Net-(R9-Pad1)") (class "Default")
      (node (ref "R9") (pin "1") (pinfunction "1_1") (pintype "passive"))
      (node (ref "U$3") (pin "36") (pinfunction "36_36") (pintype "passive"))
    )
    (net (code "64") (name "Net-(R10-Pad1)") (class "Default")
      (node (ref "R10") (pin "1") (pinfunction "1_1") (pintype "passive"))
      (node (ref "U$3") (pin "34") (pinfunction "34_34") (pintype "passive"))
    )
    (net (code "65") (name "Net-(R11-Pad1)") (class "Default")
      (node (ref "R11") (pin "1") (pinfunction "1_1") (pintype "passive"))
      (node (ref "U$3") (pin "32") (pinfunction "32_32") (pintype "passive"))
    )
    (net (code "66") (name "Net-(R14-Pad1)") (class "Default")
      (node (ref "R14") (pin "1") (pinfunction "1_1") (pintype "passive"))
      (node (ref "U$3") (pin "30") (pinfunction "30_30") (pintype "passive"))
    )
    (net (code "67") (name "Net-(R15-Pad1)") (class "Default")
      (node (ref "R15") (pin "1") (pinfunction "1_1") (pintype "passive"))
      (node (ref "U$3") (pin "28") (pinfunction "28_28") (pintype "passive"))
    )
    (net (code "68") (name "Net-(R16-Pad1)") (class "Default")
      (node (ref "R16") (pin "1") (pinfunction "1_1") (pintype "passive"))
      (node (ref "U$3") (pin "26") (pinfunction "26_26") (pintype "passive"))
    )
    (net (code "69") (name "Net-(R17-Pad1)") (class "Default")
      (node (ref "R17") (pin "1") (pinfunction "1_1") (pintype "passive"))
      (node (ref "U$3") (pin "24") (pinfunction "24_24") (pintype "passive"))
    )
    (net (code "70") (name "Net-(R18-Pad1)") (class "Default")
      (node (ref "R18") (pin "1") (pinfunction "1_1") (pintype "passive"))
      (node (ref "U$3") (pin "18") (pinfunction "18_18") (pintype "passive"))
    )
    (net (code "71") (name "Net-(R19-Pad1)") (class "Default")
      (node (ref "R19") (pin "1") (pinfunction "1_1") (pintype "passive"))
      (node (ref "U$3") (pin "16") (pinfunction "16_16") (pintype "passive"))
    )
    (net (code "72") (name "Net-(R20-Pad1)") (class "Default")
      (node (ref "R20") (pin "1") (pinfunction "1_1") (pintype "passive"))
      (node (ref "U$3") (pin "14") (pinfunction "14_14") (pintype "passive"))
    )
    (net (code "73") (name "Net-(R21-Pad1)") (class "Default")
      (node (ref "R21") (pin "1") (pinfunction "1_1") (pintype "passive"))
      (node (ref "U$3") (pin "64") (pinfunction "64_64") (pintype "passive"))
    )
    (net (code "74") (name "Net-(R22-Pad1)") (class "Default")
      (node (ref "R22") (pin "1") (pinfunction "1_1") (pintype "passive"))
      (node (ref "U$3") (pin "62") (pinfunction "62_62") (pintype "passive"))
    )
    (net (code "75") (name "Net-(R23-Pad1)") (class "Default")
      (node (ref "R23") (pin "1") (pinfunction "1_1") (pintype "passive"))
      (node (ref "U$3") (pin "60") (pinfunction "60_60") (pintype "passive"))
    )
    (net (code "76") (name "Net-(R24-Pad1)") (class "Default")
      (node (ref "R24") (pin "1") (pinfunction "1_1") (pintype "passive"))
      (node (ref "U$3") (pin "58") (pinfunction "58_58") (pintype "passive"))
    )
    (net (code "77") (name "Net-(R25-Pad1)") (class "Default")
      (node (ref "R25") (pin "1") (pinfunction "1_1") (pintype "passive"))
      (node (ref "U$3") (pin "56") (pinfunction "56_56") (pintype "passive"))
    )
    (net (code "78") (name "Net-(R26-Pad1)") (class "Default")
      (node (ref "R26") (pin "1") (pinfunction "1_1") (pintype "passive"))
      (node (ref "U$3") (pin "54") (pinfunction "54_54") (pintype "passive"))
    )
    (net (code "79") (name "Net-(R27-Pad1)") (class "Default")
      (node (ref "R27") (pin "1") (pinfunction "1_1") (pintype "passive"))
      (node (ref "U$3") (pin "52") (pinfunction "52_52") (pintype "passive"))
    )
    (net (code "80") (name "Net-(R28-Pad1)") (class "Default")
      (node (ref "R28") (pin "1") (pinfunction "1_1") (pintype "passive"))
      (node (ref "U$3") (pin "50") (pinfunction "50_50") (pintype "passive"))
    )
    (net (code "81") (name "Net-(R29-Pad1)") (class "Default")
      (node (ref "R29") (pin "1") (pinfunction "1_1") (pintype "passive"))
      (node (ref "U$3") (pin "48") (pinfunction "48_48") (pintype "passive"))
    )
    (net (code "82") (name "Net-(R30-Pad1)") (class "Default")
      (node (ref "R30") (pin "1") (pinfunction "1_1") (pintype "passive"))
      (node (ref "VD1") (pin "A") (pinfunction "A_A") (pintype "passive"))
    )
    (net (code "83") (name "Net-(R31-Pad1)") (class "Default")
      (node (ref "R31") (pin "1") (pinfunction "1_1") (pintype "passive"))
      (node (ref "U$3") (pin "46") (pinfunction "46_46") (pintype "passive"))
    )
    (net (code "84") (name "Net-(R32-Pad1)") (class "Default")
      (node (ref "R32") (pin "1") (pinfunction "1_1") (pintype "passive"))
      (node (ref "U$3") (pin "44") (pinfunction "44_44") (pintype "passive"))
    )
    (net (code "85") (name "Net-(R33-Pad1)") (class "Default")
      (node (ref "R33") (pin "1") (pinfunction "1_1") (pintype "passive"))
      (node (ref "U$3") (pin "42") (pinfunction "42_42") (pintype "passive"))
    )
    (net (code "86") (name "Net-(R34-Pad1)") (class "Default")
      (node (ref "R34") (pin "1") (pinfunction "1_1") (pintype "passive"))
      (node (ref "U$3") (pin "8") (pinfunction "8_8") (pintype "passive"))
    )
    (net (code "87") (name "Net-(R35-Pad1)") (class "Default")
      (node (ref "R35") (pin "1") (pinfunction "1_1") (pintype "passive"))
      (node (ref "U$3") (pin "6") (pinfunction "6_6") (pintype "passive"))
    )
    (net (code "88") (name "Net-(R36-Pad1)") (class "Default")
      (node (ref "R36") (pin "1") (pinfunction "1_1") (pintype "passive"))
      (node (ref "U$3") (pin "4") (pinfunction "4_4") (pintype "passive"))
    )
    (net (code "89") (name "Net-(R37-Pad1)") (class "Default")
      (node (ref "R37") (pin "1") (pinfunction "1_1") (pintype "passive"))
      (node (ref "U$3") (pin "2") (pinfunction "2_2") (pintype "passive"))
    )
    (net (code "90") (name "Net-(R60-Pad1)") (class "Default")
      (node (ref "R60") (pin "1") (pinfunction "1_1") (pintype "passive"))
      (node (ref "VD2") (pin "A") (pinfunction "A_A") (pintype "passive"))
    )
    (net (code "91") (name "Net-(U$4-PH0(OSC_IN))") (class "Default")
      (node (ref "C12") (pin "2") (pinfunction "2_2") (pintype "passive"))
      (node (ref "U$4") (pin "29") (pinfunction "PH0(OSC_IN)_29") (pintype "bidirectional"))
      (node (ref "ZQ1") (pin "3") (pinfunction "2_3") (pintype "passive"))
    )
    (net (code "92") (name "Net-(U$4-PH1(OSC_OUT))") (class "Default")
      (node (ref "C11") (pin "2") (pinfunction "2_2") (pintype "passive"))
      (node (ref "U$4") (pin "30") (pinfunction "PH1(OSC_OUT)_30") (pintype "bidirectional"))
      (node (ref "ZQ1") (pin "1") (pinfunction "1_1") (pintype "passive"))
    )
    (net (code "93") (name "Net-(U$4-VCAP_1)") (class "Default")
      (node (ref "C7") (pin "2") (pinfunction "2_2") (pintype "passive"))
      (node (ref "U$4") (pin "81") (pinfunction "VCAP_1_81") (pintype "power_in"))
    )
    (net (code "94") (name "Net-(U$4-VCAP_2)") (class "Default")
      (node (ref "C23") (pin "2") (pinfunction "2_2") (pintype "passive"))
      (node (ref "U$4") (pin "125") (pinfunction "VCAP_2_125") (pintype "power_in"))
    )
    (net (code "95") (name "USB_DM") (class "Default")
      (node (ref "U$4") (pin "122") (pinfunction "PA11_122") (pintype "bidirectional"))
      (node (ref "X1") (pin "D-") (pinfunction "D-_D-") (pintype "bidirectional"))
    )
    (net (code "96") (name "USB_DP") (class "Default")
      (node (ref "U$4") (pin "123") (pinfunction "PA12_123") (pintype "bidirectional"))
      (node (ref "X1") (pin "D+") (pinfunction "D+_D+") (pintype "bidirectional"))
    )
    (net (code "97") (name "USB_PRESENT") (class "Default")
      (node (ref "R1") (pin "1") (pinfunction "1_1") (pintype "passive"))
      (node (ref "U$4") (pin "120") (pinfunction "PA9_120") (pintype "bidirectional"))
    )
    (net (code "98") (name "unconnected-(U$4-BOOT_1(PB2)-Pad58)") (class "Default")
      (node (ref "U$4") (pin "58") (pinfunction "BOOT_1(PB2)_58") (pintype "bidirectional"))
    )
    (net (code "99") (name "unconnected-(U$4-PA0-Pad40)") (class "Default")
      (node (ref "U$4") (pin "40") (pinfunction "PA0_40") (pintype "bidirectional"))
    )
    (net (code "100") (name "unconnected-(U$4-PA1-Pad41)") (class "Default")
      (node (ref "U$4") (pin "41") (pinfunction "PA1_41") (pintype "bidirectional"))
    )
    (net (code "101") (name "unconnected-(U$4-PA2-Pad42)") (class "Default")
      (node (ref "U$4") (pin "42") (pinfunction "PA2_42") (pintype "bidirectional"))
    )
    (net (code "102") (name "unconnected-(U$4-PA3-Pad47)") (class "Default")
      (node (ref "U$4") (pin "47") (pinfunction "PA3_47") (pintype "bidirectional"))
    )
    (net (code "103") (name "unconnected-(U$4-PA4-Pad50)") (class "Default")
      (node (ref "U$4") (pin "50") (pinfunction "PA4_50") (pintype "bidirectional"))
    )
    (net (code "104") (name "unconnected-(U$4-PA5-Pad51)") (class "Default")
      (node (ref "U$4") (pin "51") (pinfunction "PA5_51") (pintype "bidirectional"))
    )
    (net (code "105") (name "unconnected-(U$4-PA6-Pad52)") (class "Default")
      (node (ref "U$4") (pin "52") (pinfunction "PA6_52") (pintype "bidirectional"))
    )
    (net (code "106") (name "unconnected-(U$4-PA7-Pad53)") (class "Default")
      (node (ref "U$4") (pin "53") (pinfunction "PA7_53") (pintype "bidirectional"))
    )
    (net (code "107") (name "unconnected-(U$4-PA8-Pad119)") (class "Default")
      (node (ref "U$4") (pin "119") (pinfunction "PA8_119") (pintype "bidirectional"))
    )
    (net (code "108") (name "unconnected-(U$4-PA10-Pad121)") (class "Default")
      (node (ref "U$4") (pin "121") (pinfunction "PA10_121") (pintype "bidirectional"))
    )
    (net (code "109") (name "unconnected-(U$4-PB0-Pad56)") (class "Default")
      (node (ref "U$4") (pin "56") (pinfunction "PB0_56") (pintype "bidirectional"))
    )
    (net (code "110") (name "unconnected-(U$4-PB1-Pad57)") (class "Default")
      (node (ref "U$4") (pin "57") (pinfunction "PB1_57") (pintype "bidirectional"))
    )
    (net (code "111") (name "unconnected-(U$4-PB5-Pad163)") (class "Default")
      (node (ref "U$4") (pin "163") (pinfunction "PB5_163") (pintype "bidirectional"))
    )
    (net (code "112") (name "unconnected-(U$4-PB6-Pad164)") (class "Default")
      (node (ref "U$4") (pin "164") (pinfunction "PB6_164") (pintype "bidirectional"))
    )
    (net (code "113") (name "unconnected-(U$4-PB7-Pad165)") (class "Default")
      (node (ref "U$4") (pin "165") (pinfunction "PB7_165") (pintype "bidirectional"))
    )
    (net (code "114") (name "unconnected-(U$4-PB8-Pad167)") (class "Default")
      (node (ref "U$4") (pin "167") (pinfunction "PB8_167") (pintype "bidirectional"))
    )
    (net (code "115") (name "unconnected-(U$4-PB9-Pad168)") (class "Default")
      (node (ref "U$4") (pin "168") (pinfunction "PB9_168") (pintype "bidirectional"))
    )
    (net (code "116") (name "unconnected-(U$4-PB10-Pad79)") (class "Default")
      (node (ref "U$4") (pin "79") (pinfunction "PB10_79") (pintype "bidirectional"))
    )
    (net (code "117") (name "unconnected-(U$4-PB11-Pad80)") (class "Default")
      (node (ref "U$4") (pin "80") (pinfunction "PB11_80") (pintype "bidirectional"))
    )
    (net (code "118") (name "unconnected-(U$4-PB12-Pad92)") (class "Default")
      (node (ref "U$4") (pin "92") (pinfunction "PB12_92") (pintype "bidirectional"))
    )
    (net (code "119") (name "unconnected-(U$4-PB13-Pad93)") (class "Default")
      (node (ref "U$4") (pin "93") (pinfunction "PB13_93") (pintype "bidirectional"))
    )
    (net (code "120") (name "unconnected-(U$4-PB14-Pad94)") (class "Default")
      (node (ref "U$4") (pin "94") (pinfunction "PB14_94") (pintype "bidirectional"))
    )
    (net (code "121") (name "unconnected-(U$4-PB15-Pad95)") (class "Default")
      (node (ref "U$4") (pin "95") (pinfunction "PB15_95") (pintype "bidirectional"))
    )
    (net (code "122") (name "unconnected-(U$4-PC0-Pad32)") (class "Default")
      (node (ref "U$4") (pin "32") (pinfunction "PC0_32") (pintype "bidirectional"))
    )
    (net (code "123") (name "unconnected-(U$4-PC1-Pad33)") (class "Default")
      (node (ref "U$4") (pin "33") (pinfunction "PC1_33") (pintype "bidirectional"))
    )
    (net (code "124") (name "unconnected-(U$4-PC2-Pad34)") (class "Default")
      (node (ref "U$4") (pin "34") (pinfunction "PC2_34") (pintype "bidirectional"))
    )
    (net (code "125") (name "unconnected-(U$4-PC3-Pad35)") (class "Default")
      (node (ref "U$4") (pin "35") (pinfunction "PC3_35") (pintype "bidirectional"))
    )
    (net (code "126") (name "unconnected-(U$4-PC4-Pad54)") (class "Default")
      (node (ref "U$4") (pin "54") (pinfunction "PC4_54") (pintype "bidirectional"))
    )
    (net (code "127") (name "unconnected-(U$4-PC5-Pad55)") (class "Default")
      (node (ref "U$4") (pin "55") (pinfunction "PC5_55") (pintype "bidirectional"))
    )
    (net (code "128") (name "unconnected-(U$4-PC6-Pad115)") (class "Default")
      (node (ref "U$4") (pin "115") (pinfunction "PC6_115") (pintype "bidirectional"))
    )
    (net (code "129") (name "unconnected-(U$4-PC7-Pad116)") (class "Default")
      (node (ref "U$4") (pin "116") (pinfunction "PC7_116") (pintype "bidirectional"))
    )
    (net (code "130") (name "unconnected-(U$4-PC8-Pad117)") (class "Default")
      (node (ref "U$4") (pin "117") (pinfunction "PC8_117") (pintype "bidirectional"))
    )
    (net (code "131") (name "unconnected-(U$4-PC9-Pad118)") (class "Default")
      (node (ref "U$4") (pin "118") (pinfunction "PC9_118") (pintype "bidirectional"))
    )
    (net (code "132") (name "unconnected-(U$4-PC10-Pad139)") (class "Default")
      (node (ref "U$4") (pin "139") (pinfunction "PC10_139") (pintype "bidirectional"))
    )
    (net (code "133") (name "unconnected-(U$4-PC11-Pad140)") (class "Default")
      (node (ref "U$4") (pin "140") (pinfunction "PC11_140") (pintype "bidirectional"))
    )
    (net (code "134") (name "unconnected-(U$4-PC12-Pad141)") (class "Default")
      (node (ref "U$4") (pin "141") (pinfunction "PC12_141") (pintype "bidirectional"))
    )
    (net (code "135") (name "unconnected-(U$4-PC13(TAMPER-RTC)-Pad8)") (class "Default")
      (node (ref "U$4") (pin "8") (pinfunction "PC13(TAMPER-RTC)_8") (pintype "bidirectional"))
    )
    (net (code "136") (name "unconnected-(U$4-PC14(OSC32_IN)-Pad9)") (class "Default")
      (node (ref "U$4") (pin "9") (pinfunction "PC14(OSC32_IN)_9") (pintype "bidirectional"))
    )
    (net (code "137") (name "unconnected-(U$4-PC15(OSC32_OUT)-Pad10)") (class "Default")
      (node (ref "U$4") (pin "10") (pinfunction "PC15(OSC32_OUT)_10") (pintype "bidirectional"))
    )
    (net (code "138") (name "unconnected-(U$4-PD2-Pad144)") (class "Default")
      (node (ref "U$4") (pin "144") (pinfunction "PD2_144") (pintype "bidirectional"))
    )
    (net (code "139") (name "unconnected-(U$4-PD3-Pad145)") (class "Default")
      (node (ref "U$4") (pin "145") (pinfunction "PD3_145") (pintype "bidirectional"))
    )
    (net (code "140") (name "unconnected-(U$4-PD6-Pad150)") (class "Default")
      (node (ref "U$4") (pin "150") (pinfunction "PD6_150") (pintype "bidirectional"))
    )
    (net (code "141") (name "unconnected-(U$4-PD11-Pad99)") (class "Default")
      (node (ref "U$4") (pin "99") (pinfunction "PD11_99") (pintype "bidirectional"))
    )
    (net (code "142") (name "unconnected-(U$4-PD12-Pad100)") (class "Default")
      (node (ref "U$4") (pin "100") (pinfunction "PD12_100") (pintype "bidirectional"))
    )
    (net (code "143") (name "unconnected-(U$4-PD13-Pad101)") (class "Default")
      (node (ref "U$4") (pin "101") (pinfunction "PD13_101") (pintype "bidirectional"))
    )
    (net (code "144") (name "unconnected-(U$4-PE2-Pad1)") (class "Default")
      (node (ref "U$4") (pin "1") (pinfunction "PE2_1") (pintype "bidirectional"))
    )
    (net (code "145") (name "unconnected-(U$4-PE3-Pad2)") (class "Default")
      (node (ref "U$4") (pin "2") (pinfunction "PE3_2") (pintype "bidirectional"))
    )
    (net (code "146") (name "unconnected-(U$4-PF6-Pad24)") (class "Default")
      (node (ref "U$4") (pin "24") (pinfunction "PF6_24") (pintype "bidirectional"))
    )
    (net (code "147") (name "unconnected-(U$4-PF7-Pad25)") (class "Default")
      (node (ref "U$4") (pin "25") (pinfunction "PF7_25") (pintype "bidirectional"))
    )
    (net (code "148") (name "unconnected-(U$4-PF8-Pad26)") (class "Default")
      (node (ref "U$4") (pin "26") (pinfunction "PF8_26") (pintype "bidirectional"))
    )
    (net (code "149") (name "unconnected-(U$4-PF9-Pad27)") (class "Default")
      (node (ref "U$4") (pin "27") (pinfunction "PF9_27") (pintype "bidirectional"))
    )
    (net (code "150") (name "unconnected-(U$4-PF10-Pad28)") (class "Default")
      (node (ref "U$4") (pin "28") (pinfunction "PF10_28") (pintype "bidirectional"))
    )
    (net (code "151") (name "unconnected-(U$4-PF11-Pad59)") (class "Default")
      (node (ref "U$4") (pin "59") (pinfunction "PF11_59") (pintype "bidirectional"))
    )
    (net (code "152") (name "unconnected-(U$4-PG6-Pad110)") (class "Default")
      (node (ref "U$4") (pin "110") (pinfunction "PG6_110") (pintype "bidirectional"))
    )
    (net (code "153") (name "unconnected-(U$4-PG7-Pad111)") (class "Default")
      (node (ref "U$4") (pin "111") (pinfunction "PG7_111") (pintype "bidirectional"))
    )
    (net (code "154") (name "unconnected-(U$4-PG8-Pad112)") (class "Default")
      (node (ref "U$4") (pin "112") (pinfunction "PG8_112") (pintype "bidirectional"))
    )
    (net (code "155") (name "unconnected-(U$4-PG9-Pad152)") (class "Default")
      (node (ref "U$4") (pin "152") (pinfunction "PG9_152") (pintype "bidirectional"))
    )
    (net (code "156") (name "unconnected-(U$4-PG10-Pad153)") (class "Default")
      (node (ref "U$4") (pin "153") (pinfunction "PG10_153") (pintype "bidirectional"))
    )
    (net (code "157") (name "unconnected-(U$4-PG11-Pad154)") (class "Default")
      (node (ref "U$4") (pin "154") (pinfunction "PG11_154") (pintype "bidirectional"))
    )
    (net (code "158") (name "unconnected-(U$4-PG12-Pad155)") (class "Default")
      (node (ref "U$4") (pin "155") (pinfunction "PG12_155") (pintype "bidirectional"))
    )
    (net (code "159") (name "unconnected-(U$4-PG13-Pad156)") (class "Default")
      (node (ref "U$4") (pin "156") (pinfunction "PG13_156") (pintype "bidirectional"))
    )
    (net (code "160") (name "unconnected-(U$4-PG14-Pad157)") (class "Default")
      (node (ref "U$4") (pin "157") (pinfunction "PG14_157") (pintype "bidirectional"))
    )
    (net (code "161") (name "unconnected-(U$4-PG15-Pad160)") (class "Default")
      (node (ref "U$4") (pin "160") (pinfunction "PG15_160") (pintype "bidirectional"))
    )
    (net (code "162") (name "unconnected-(U$4-PH2-Pad43)") (class "Default")
      (node (ref "U$4") (pin "43") (pinfunction "PH2_43") (pintype "bidirectional"))
    )
    (net (code "163") (name "unconnected-(U$4-PH3-Pad44)") (class "Default")
      (node (ref "U$4") (pin "44") (pinfunction "PH3_44") (pintype "bidirectional"))
    )
    (net (code "164") (name "unconnected-(U$4-PH4-Pad45)") (class "Default")
      (node (ref "U$4") (pin "45") (pinfunction "PH4_45") (pintype "bidirectional"))
    )
    (net (code "165") (name "unconnected-(U$4-PH5-Pad46)") (class "Default")
      (node (ref "U$4") (pin "46") (pinfunction "PH5_46") (pintype "bidirectional"))
    )
    (net (code "166") (name "unconnected-(U$4-PH6-Pad83)") (class "Default")
      (node (ref "U$4") (pin "83") (pinfunction "PH6_83") (pintype "bidirectional"))
    )
    (net (code "167") (name "unconnected-(U$4-PH7-Pad84)") (class "Default")
      (node (ref "U$4") (pin "84") (pinfunction "PH7_84") (pintype "bidirectional"))
    )
    (net (code "168") (name "unconnected-(U$4-PH8-Pad85)") (class "Default")
      (node (ref "U$4") (pin "85") (pinfunction "PH8_85") (pintype "bidirectional"))
    )
    (net (code "169") (name "unconnected-(U$4-PH9-Pad86)") (class "Default")
      (node (ref "U$4") (pin "86") (pinfunction "PH9_86") (pintype "bidirectional"))
    )
    (net (code "170") (name "unconnected-(U$4-PH10-Pad87)") (class "Default")
      (node (ref "U$4") (pin "87") (pinfunction "PH10_87") (pintype "bidirectional"))
    )
    (net (code "171") (name "unconnected-(U$4-PH11-Pad88)") (class "Default")
      (node (ref "U$4") (pin "88") (pinfunction "PH11_88") (pintype "bidirectional"))
    )
    (net (code "172") (name "unconnected-(U$4-PH12-Pad89)") (class "Default")
      (node (ref "U$4") (pin "89") (pinfunction "PH12_89") (pintype "bidirectional"))
    )
    (net (code "173") (name "unconnected-(U$4-PH13-Pad128)") (class "Default")
      (node (ref "U$4") (pin "128") (pinfunction "PH13_128") (pintype "bidirectional"))
    )
    (net (code "174") (name "unconnected-(U$4-PH14-Pad129)") (class "Default")
      (node (ref "U$4") (pin "129") (pinfunction "PH14_129") (pintype "bidirectional"))
    )
    (net (code "175") (name "unconnected-(U$4-PH15-Pad130)") (class "Default")
      (node (ref "U$4") (pin "130") (pinfunction "PH15_130") (pintype "bidirectional"))
    )
    (net (code "176") (name "unconnected-(U$4-PI0-Pad131)") (class "Default")
      (node (ref "U$4") (pin "131") (pinfunction "PI0_131") (pintype "bidirectional"))
    )
    (net (code "177") (name "unconnected-(U$4-PI1-Pad132)") (class "Default")
      (node (ref "U$4") (pin "132") (pinfunction "PI1_132") (pintype "bidirectional"))
    )
    (net (code "178") (name "unconnected-(U$4-PI4-Pad173)") (class "Default")
      (node (ref "U$4") (pin "173") (pinfunction "PI4_173") (pintype "bidirectional"))
    )
    (net (code "179") (name "unconnected-(U$4-PI5-Pad174)") (class "Default")
      (node (ref "U$4") (pin "174") (pinfunction "PI5_174") (pintype "bidirectional"))
    )
    (net (code "180") (name "unconnected-(U$4-PI6-Pad175)") (class "Default")
      (node (ref "U$4") (pin "175") (pinfunction "PI6_175") (pintype "bidirectional"))
    )
    (net (code "181") (name "unconnected-(U$4-PI7-Pad176)") (class "Default")
      (node (ref "U$4") (pin "176") (pinfunction "PI7_176") (pintype "bidirectional"))
    )
    (net (code "182") (name "unconnected-(U$4-PI8-Pad7)") (class "Default")
      (node (ref "U$4") (pin "7") (pinfunction "PI8_7") (pintype "bidirectional"))
    )
    (net (code "183") (name "unconnected-(U$4-PI9-Pad11)") (class "Default")
      (node (ref "U$4") (pin "11") (pinfunction "PI9_11") (pintype "bidirectional"))
    )
    (net (code "184") (name "unconnected-(U$4-PI10-Pad12)") (class "Default")
      (node (ref "U$4") (pin "12") (pinfunction "PI10_12") (pintype "bidirectional"))
    )
    (net (code "185") (name "unconnected-(U$4-PI11-Pad13)") (class "Default")
      (node (ref "U$4") (pin "13") (pinfunction "PI11_13") (pintype "bidirectional"))
    )
    (net (code "186") (name "unconnected-(XP1-Pad11)") (class "Default")
      (node (ref "XP1") (pin "11") (pinfunction "11_11") (pintype "passive"))
    )
    (net (code "187") (name "unconnected-(XP1-Pad17)") (class "Default")
      (node (ref "XP1") (pin "17") (pinfunction "17_17") (pintype "passive"))
    )
    (net (code "188") (name "unconnected-(XP1-Pad19)") (class "Default")
      (node (ref "XP1") (pin "19") (pinfunction "19_19") (pintype "passive"))
    )
  )
)
